# Analog.net
KiCad netlist of a schematic drawn in Altium Designer
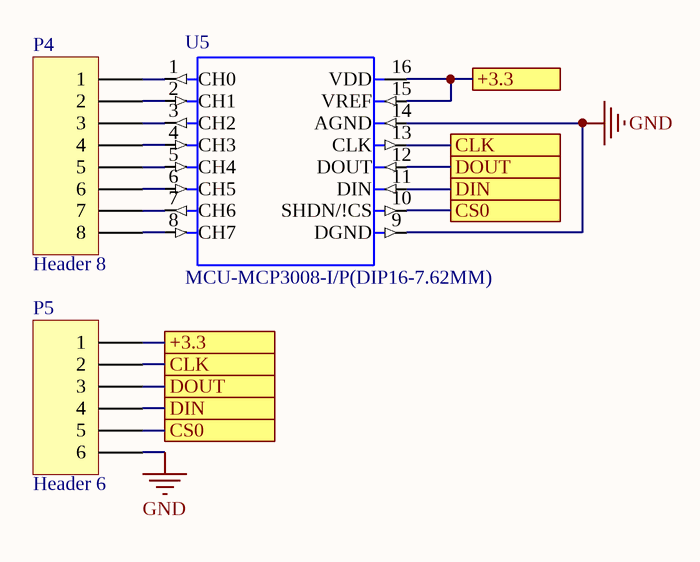
[diagram p0: Analog.SchDoc]

(export (version "E")
  (design (tool "Eeschema 10.0.6"))
  (components
    (comp (ref "P4")
      (value "Header 8")
      (footprint "HDR1X8")
      (description "Header, 8-Pin")
      (fields (field (name "PUBLISHER") "Altium Limited"))
      (libsource (lib "Miscellaneous Connectors") (part "Header 8"))
    )
    (comp (ref "P5")
      (value "Header 6")
      (footprint "HDR1X6")
      (description "Header, 6-Pin")
      (fields (field (name "PUBLISHER") "Altium Limited"))
      (libsource (lib "Miscellaneous Connectors") (part "Header 6"))
    )
    (comp (ref "U5")
      (value "MCU-MCP3008-I/P(DIP16-7.62MM)")
      (footprint "DIP16-2.54-19.2X7.62MM")
      (description "10 Bit Analog to Digital Converter 4, 8 Input 1 SAR 16-PDIP")
      (fields (field (name "MF") "Microchip") (field (name "MP") "MCP3008-I/P"))
      (libsource (lib "MCU-MCP3008-I_P_DIP16-7.62MM_") (part "MCU-MCP3008-I/P(DIP16-7.62MM)"))
    )
  )
  (nets
    (net (code "1") (name "/+3.3") (class "Default")
      (node (ref "P5") (pin "1") (pinfunction "1_1") (pintype "passive"))
      (node (ref "U5") (pin "15") (pinfunction "VREF_15") (pintype "input"))
      (node (ref "U5") (pin "16") (pinfunction "VDD_16") (pintype "power_in"))
    )
    (net (code "2") (name "/CLK") (class "Default")
      (node (ref "P5") (pin "2") (pinfunction "2_2") (pintype "passive"))
      (node (ref "U5") (pin "13") (pinfunction "CLK_13") (pintype "output"))
    )
    (net (code "3") (name "/CS0") (class "Default")
      (node (ref "P5") (pin "5") (pinfunction "5_5") (pintype "passive"))
      (node (ref "U5") (pin "10") (pinfunction "SHDN/!CS_10") (pintype "output"))
    )
    (net (code "4") (name "/DIN") (class "Default")
      (node (ref "P5") (pin "4") (pinfunction "4_4") (pintype "passive"))
      (node (ref "U5") (pin "11") (pinfunction "DIN_11") (pintype "input"))
    )
    (net (code "5") (name "/DOUT") (class "Default")
      (node (ref "P5") (pin "3") (pinfunction "3_3") (pintype "passive"))
      (node (ref "U5") (pin "12") (pinfunction "DOUT_12") (pintype "input"))
    )
    (net (code "6") (name "GND") (class "Default")
      (node (ref "P5") (pin "6") (pinfunction "6_6") (pintype "passive"))
      (node (ref "U5") (pin "14") (pinfunction "AGND_14") (pintype "input"))
      (node (ref "U5") (pin "9") (pinfunction "DGND_9") (pintype "output"))
    )
    (net (code "7") (name "Net-(U5-CH0)") (class "Default")
      (node (ref "P4") (pin "1") (pinfunction "1_1") (pintype "passive"))
      (node (ref "U5") (pin "1") (pinfunction "CH0_1") (pintype "output"))
    )
    (net (code "8") (name "Net-(U5-CH1)") (class "Default")
      (node (ref "P4") (pin "2") (pinfunction "2_2") (pintype "passive"))
      (node (ref "U5") (pin "2") (pinfunction "CH1_2") (pintype "input"))
    )
    (net (code "9") (name "Net-(U5-CH2)") (class "Default")
      (node (ref "P4") (pin "3") (pinfunction "3_3") (pintype "passive"))
      (node (ref "U5") (pin "3") (pinfunction "CH2_3") (pintype "output"))
    )
    (net (code "10") (name "Net-(U5-CH3)") (class "Default")
      (node (ref "P4") (pin "4") (pinfunction "4_4") (pintype "passive"))
      (node (ref "U5") (pin "4") (pinfunction "CH3_4") (pintype "input"))
    )
    (net (code "11") (name "Net-(U5-CH4)") (class "Default")
      (node (ref "P4") (pin "5") (pinfunction "5_5") (pintype "passive"))
      (node (ref "U5") (pin "5") (pinfunction "CH4_5") (pintype "input"))
    )
    (net (code "12") (name "Net-(U5-CH5)") (class "Default")
      (node (ref "P4") (pin "6") (pinfunction "6_6") (pintype "passive"))
      (node (ref "U5") (pin "6") (pinfunction "CH5_6") (pintype "input"))
    )
    (net (code "13") (name "Net-(U5-CH6)") (class "Default")
      (node (ref "P4") (pin "7") (pinfunction "7_7") (pintype "passive"))
      (node (ref "U5") (pin "7") (pinfunction "CH6_7") (pintype "output"))
    )
    (net (code "14") (name "Net-(U5-CH7)") (class "Default")
      (node (ref "P4") (pin "8") (pinfunction "8_8") (pintype "passive"))
      (node (ref "U5") (pin "8") (pinfunction "CH7_8") (pintype "input"))
    )
  )
)
